# Adjustable_Led_Driver_on_LM-317.net
KiCad netlist of a schematic drawn in Altium Designer
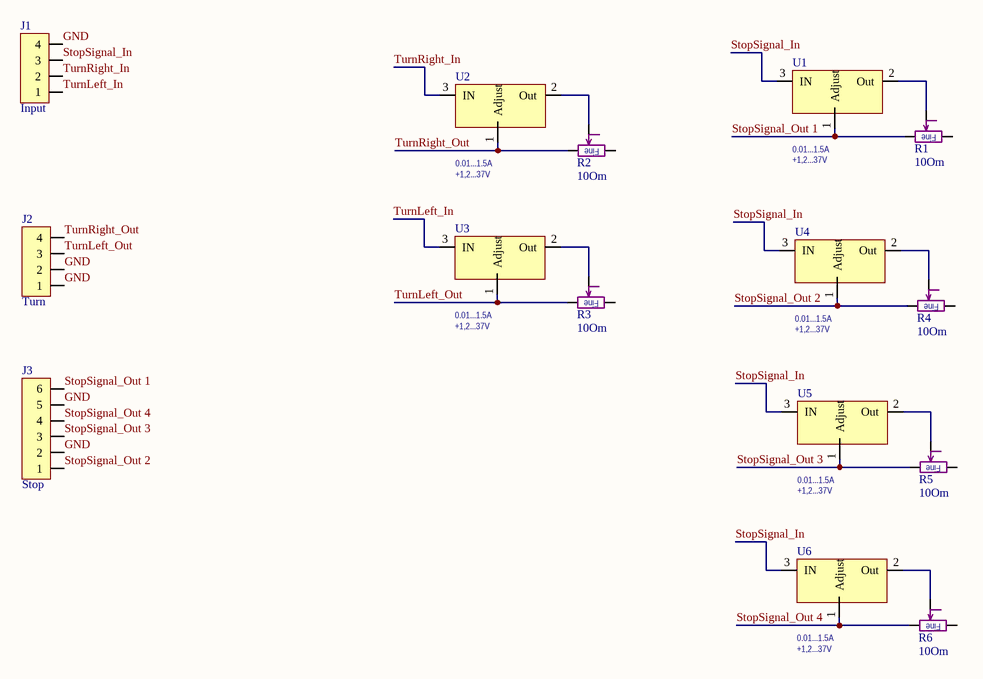
[diagram p0: Adjustable Led Driver on LM-317 (6 ports).SchDoc]

(export (version "E")
  (design (tool "Eeschema 10.0.6"))
  (components
    (comp (ref "J1")
      (value "Input")
      (footprint "Connector:Molex Micro-Fit 3.0 - 4 pin D R")
      (description "Horisontal, Dbl line, Male - 3mm")
      (fields (field (name "PART NUMBER") "0430450402"))
      (libsource (lib "Connector") (part "Micro-Fit 4R (2x2)"))
    )
    (comp (ref "J2")
      (value "Turn")
      (footprint "Connector:Molex Micro-Fit 3.0 - 4 pin D R")
      (description "Horisontal, Dbl line, Male - 3mm")
      (fields (field (name "PART NUMBER") "0430450402"))
      (libsource (lib "Connector") (part "Micro-Fit 4R (2x2)"))
    )
    (comp (ref "J3")
      (value "Stop")
      (footprint "Connector:Molex Micro-Fit 3.0 - 6 pin D R")
      (description "Horisontal, Dbl line, Male - 3mm")
      (libsource (lib "Connector") (part "Micro-Fit 6R (2x3)"))
    )
    (comp (ref "R1")
      (value "10Om")
      (footprint "PassiveComponents:Res Adj 2.54 X 3")
      (libsource (lib "PassiveComponents") (part "Res Adj 3296"))
    )
    (comp (ref "R2")
      (value "10Om")
      (footprint "PassiveComponents:Res Adj 2.54 X 3")
      (libsource (lib "PassiveComponents") (part "Res Adj 3296"))
    )
    (comp (ref "R3")
      (value "10Om")
      (footprint "PassiveComponents:Res Adj 2.54 X 3")
      (libsource (lib "PassiveComponents") (part "Res Adj 3296"))
    )
    (comp (ref "R4")
      (value "10Om")
      (footprint "PassiveComponents:Res Adj 2.54 X 3")
      (libsource (lib "PassiveComponents") (part "Res Adj 3296"))
    )
    (comp (ref "R5")
      (value "10Om")
      (footprint "PassiveComponents:Res Adj 2.54 X 3")
      (libsource (lib "PassiveComponents") (part "Res Adj 3296"))
    )
    (comp (ref "R6")
      (value "10Om")
      (footprint "PassiveComponents:Res Adj 2.54 X 3")
      (libsource (lib "PassiveComponents") (part "Res Adj 3296"))
    )
    (comp (ref "U1")
      (value "~")
      (footprint "GeneralCases:TO220-2")
      (description "Voltage Regulator")
      (fields (field (name "I OUTPUT (A) ADJUSTABLE") "0.01...1.5A") (field (name "V OUT") "+1,2...37V"))
      (libsource (lib "PowerAdjusment") (part "LM-317"))
    )
    (comp (ref "U2")
      (value "~")
      (footprint "GeneralCases:TO220-2")
      (description "Voltage Regulator")
      (fields (field (name "I OUTPUT (A) ADJUSTABLE") "0.01...1.5A") (field (name "V OUT") "+1,2...37V"))
      (libsource (lib "PowerAdjusment") (part "LM-317"))
    )
    (comp (ref "U3")
      (value "~")
      (footprint "GeneralCases:TO220-2")
      (description "Voltage Regulator")
      (fields (field (name "I OUTPUT (A) ADJUSTABLE") "0.01...1.5A") (field (name "V OUT") "+1,2...37V"))
      (libsource (lib "PowerAdjusment") (part "LM-317"))
    )
    (comp (ref "U4")
      (value "~")
      (footprint "GeneralCases:TO220-2")
      (description "Voltage Regulator")
      (fields (field (name "I OUTPUT (A) ADJUSTABLE") "0.01...1.5A") (field (name "V OUT") "+1,2...37V"))
      (libsource (lib "PowerAdjusment") (part "LM-317"))
    )
    (comp (ref "U5")
      (value "~")
      (footprint "GeneralCases:TO220-2")
      (description "Voltage Regulator")
      (fields (field (name "I OUTPUT (A) ADJUSTABLE") "0.01...1.5A") (field (name "V OUT") "+1,2...37V"))
      (libsource (lib "PowerAdjusment") (part "LM-317"))
    )
    (comp (ref "U6")
      (value "~")
      (footprint "GeneralCases:TO220-2")
      (description "Voltage Regulator")
      (fields (field (name "I OUTPUT (A) ADJUSTABLE") "0.01...1.5A") (field (name "V OUT") "+1,2...37V"))
      (libsource (lib "PowerAdjusment") (part "LM-317"))
    )
  )
  (nets
    (net (code "1") (name "/GND") (class "Default")
      (node (ref "J1") (pin "4") (pinfunction "4_4") (pintype "passive"))
      (node (ref "J2") (pin "1") (pinfunction "1_1") (pintype "passive"))
      (node (ref "J2") (pin "2") (pinfunction "2_2") (pintype "passive"))
      (node (ref "J3") (pin "2") (pinfunction "2_2") (pintype "passive"))
      (node (ref "J3") (pin "5") (pinfunction "5_5") (pintype "passive"))
    )
    (net (code "2") (name "/StopSignal_In") (class "Default")
      (node (ref "J1") (pin "3") (pinfunction "3_3") (pintype "passive"))
      (node (ref "U1") (pin "3") (pinfunction "IN_3") (pintype "power_in"))
      (node (ref "U4") (pin "3") (pinfunction "IN_3") (pintype "power_in"))
      (node (ref "U5") (pin "3") (pinfunction "IN_3") (pintype "power_in"))
      (node (ref "U6") (pin "3") (pinfunction "IN_3") (pintype "power_in"))
    )
    (net (code "3") (name "/StopSignal_Out 1") (class "Default")
      (node (ref "J3") (pin "6") (pinfunction "6_6") (pintype "passive"))
      (node (ref "R1") (pin "3") (pinfunction "3_3") (pintype "passive"))
      (node (ref "U1") (pin "1") (pinfunction "Adjust_1") (pintype "passive"))
    )
    (net (code "4") (name "/StopSignal_Out 2") (class "Default")
      (node (ref "J3") (pin "1") (pinfunction "1_1") (pintype "passive"))
      (node (ref "R4") (pin "3") (pinfunction "3_3") (pintype "passive"))
      (node (ref "U4") (pin "1") (pinfunction "Adjust_1") (pintype "passive"))
    )
    (net (code "5") (name "/StopSignal_Out 3") (class "Default")
      (node (ref "J3") (pin "3") (pinfunction "3_3") (pintype "passive"))
      (node (ref "R5") (pin "3") (pinfunction "3_3") (pintype "passive"))
      (node (ref "U5") (pin "1") (pinfunction "Adjust_1") (pintype "passive"))
    )
    (net (code "6") (name "/StopSignal_Out 4") (class "Default")
      (node (ref "J3") (pin "4") (pinfunction "4_4") (pintype "passive"))
      (node (ref "R6") (pin "3") (pinfunction "3_3") (pintype "passive"))
      (node (ref "U6") (pin "1") (pinfunction "Adjust_1") (pintype "passive"))
    )
    (net (code "7") (name "/TurnLeft_In") (class "Default")
      (node (ref "J1") (pin "1") (pinfunction "1_1") (pintype "passive"))
      (node (ref "U3") (pin "3") (pinfunction "IN_3") (pintype "power_in"))
    )
    (net (code "8") (name "/TurnLeft_Out") (class "Default")
      (node (ref "J2") (pin "3") (pinfunction "3_3") (pintype "passive"))
      (node (ref "R3") (pin "3") (pinfunction "3_3") (pintype "passive"))
      (node (ref "U3") (pin "1") (pinfunction "Adjust_1") (pintype "passive"))
    )
    (net (code "9") (name "/TurnRight_In") (class "Default")
      (node (ref "J1") (pin "2") (pinfunction "2_2") (pintype "passive"))
      (node (ref "U2") (pin "3") (pinfunction "IN_3") (pintype "power_in"))
    )
    (net (code "10") (name "/TurnRight_Out") (class "Default")
      (node (ref "J2") (pin "4") (pinfunction "4_4") (pintype "passive"))
      (node (ref "R2") (pin "3") (pinfunction "3_3") (pintype "passive"))
      (node (ref "U2") (pin "1") (pinfunction "Adjust_1") (pintype "passive"))
    )
    (net (code "11") (name "Net-(U1-Out)") (class "Default")
      (node (ref "R1") (pin "2") (pinfunction "2_2") (pintype "passive"))
      (node (ref "U1") (pin "2") (pinfunction "Out_2") (pintype "power_in"))
    )
    (net (code "12") (name "Net-(U2-Out)") (class "Default")
      (node (ref "R2") (pin "2") (pinfunction "2_2") (pintype "passive"))
      (node (ref "U2") (pin "2") (pinfunction "Out_2") (pintype "power_in"))
    )
    (net (code "13") (name "Net-(U3-Out)") (class "Default")
      (node (ref "R3") (pin "2") (pinfunction "2_2") (pintype "passive"))
      (node (ref "U3") (pin "2") (pinfunction "Out_2") (pintype "power_in"))
    )
    (net (code "14") (name "Net-(U4-Out)") (class "Default")
      (node (ref "R4") (pin "2") (pinfunction "2_2") (pintype "passive"))
      (node (ref "U4") (pin "2") (pinfunction "Out_2") (pintype "power_in"))
    )
    (net (code "15") (name "Net-(U5-Out)") (class "Default")
      (node (ref "R5") (pin "2") (pinfunction "2_2") (pintype "passive"))
      (node (ref "U5") (pin "2") (pinfunction "Out_2") (pintype "power_in"))
    )
    (net (code "16") (name "Net-(U6-Out)") (class "Default")
      (node (ref "R6") (pin "2") (pinfunction "2_2") (pintype "passive"))
      (node (ref "U6") (pin "2") (pinfunction "Out_2") (pintype "power_in"))
    )
    (net (code "17") (name "unconnected-(R1-Pad1)") (class "Default")
      (node (ref "R1") (pin "1") (pinfunction "1_1") (pintype "passive"))
    )
    (net (code "18") (name "unconnected-(R2-Pad1)") (class "Default")
      (node (ref "R2") (pin "1") (pinfunction "1_1") (pintype "passive"))
    )
    (net (code "19") (name "unconnected-(R3-Pad1)") (class "Default")
      (node (ref "R3") (pin "1") (pinfunction "1_1") (pintype "passive"))
    )
    (net (code "20") (name "unconnected-(R4-Pad1)") (class "Default")
      (node (ref "R4") (pin "1") (pinfunction "1_1") (pintype "passive"))
    )
    (net (code "21") (name "unconnected-(R5-Pad1)") (class "Default")
      (node (ref "R5") (pin "1") (pinfunction "1_1") (pintype "passive"))
    )
    (net (code "22") (name "unconnected-(R6-Pad1)") (class "Default")
      (node (ref "R6") (pin "1") (pinfunction "1_1") (pintype "passive"))
    )
  )
)
